# Sheet1.net
KiCad netlist of a schematic drawn in Altium Designer
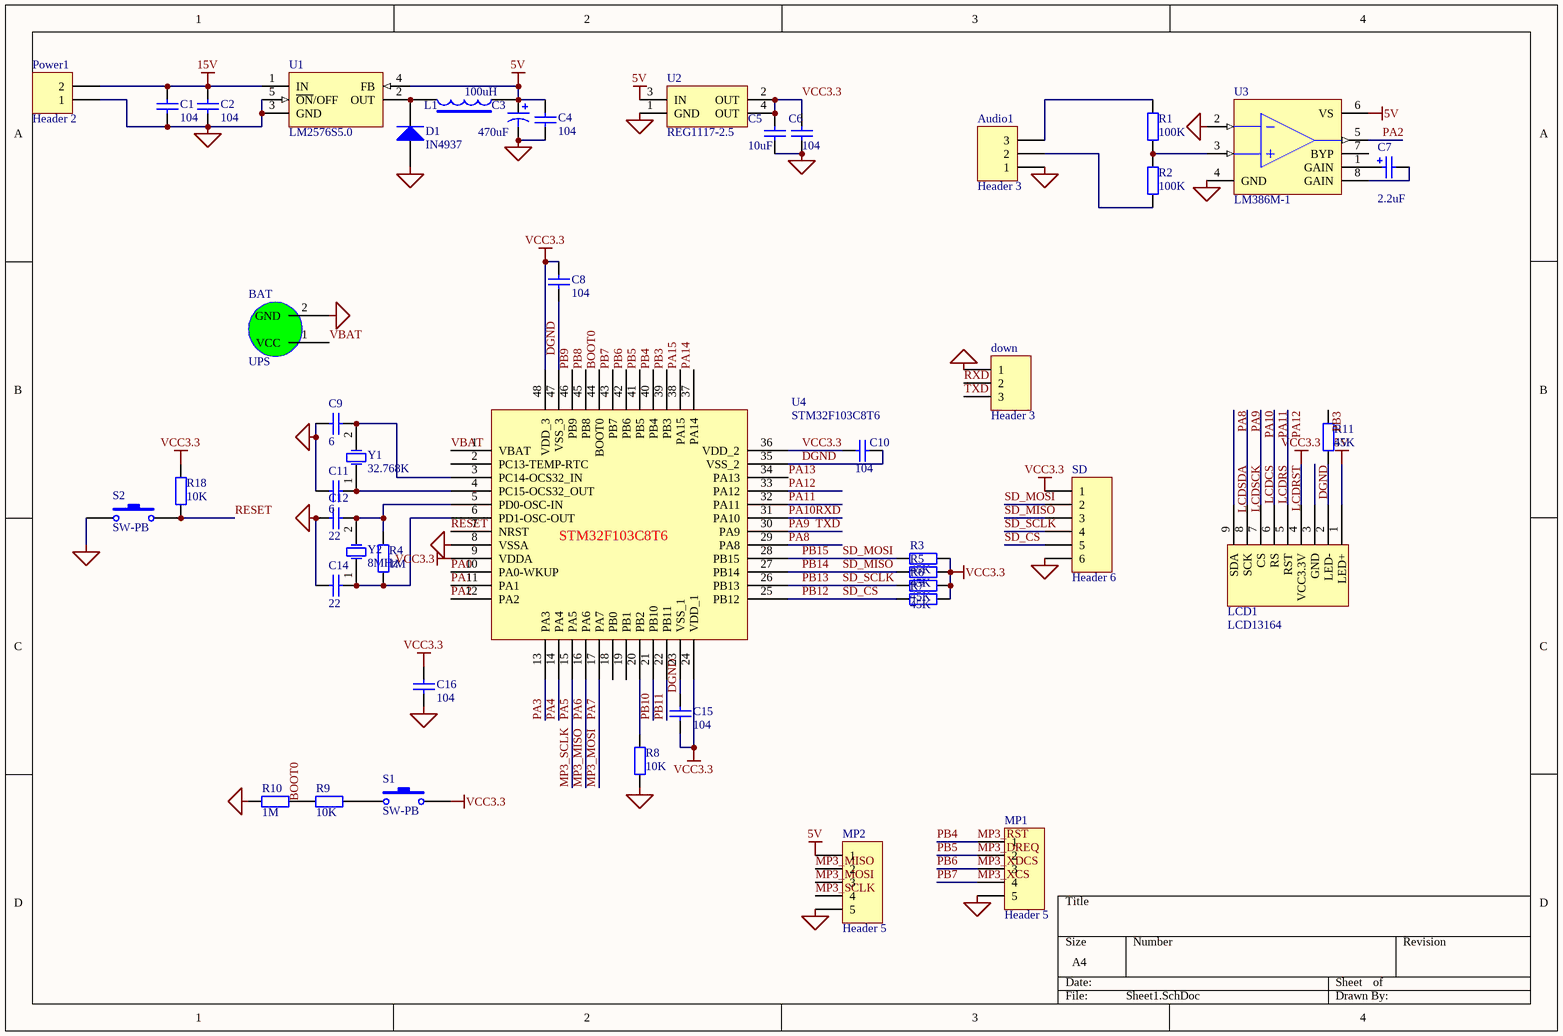
[diagram p0: Sheet1.SchDoc]

(export (version "E")
  (design (tool "Eeschema 10.0.6"))
  (components
    (comp (ref "Audio1")
      (value "Header 3")
      (footprint "HDR1X3")
      (description "Header, 3-Pin")
      (fields (field (name "PUBLISHER") "Altium Limited"))
      (libsource (lib "") (part "Header 3_1"))
    )
    (comp (ref "BAT") (value "UPS") (footprint "BAT") (libsource (lib "selfmade") (part "UPS")))
    (comp (ref "C1")
      (value "104")
      (footprint "1608[0603]")
      (description "Capacitor")
      (fields (field (name "PUBLISHER") "Altium Limited"))
      (libsource (lib "Miscellaneous Devices") (part "Cap"))
    )
    (comp (ref "C2")
      (value "104")
      (footprint "1608[0603]")
      (description "Capacitor")
      (fields (field (name "PUBLISHER") "Altium Limited"))
      (libsource (lib "Miscellaneous Devices") (part "Cap"))
    )
    (comp (ref "C3")
      (value "470uF")
      (footprint "RB.1/.2")
      (description "Polarized Capacitor (Radial)")
      (fields (field (name "PUBLISHER") "Altium Limited"))
      (libsource (lib "") (part "Cap Pol1_1"))
    )
    (comp (ref "C4")
      (value "104")
      (footprint "1608[0603]")
      (description "Capacitor")
      (fields (field (name "PUBLISHER") "Altium Limited"))
      (libsource (lib "Miscellaneous Devices") (part "Cap"))
    )
    (comp (ref "C5")
      (value "10uF")
      (footprint "2012[0805]")
      (description "Capacitor")
      (fields (field (name "PUBLISHER") "Altium Limited"))
      (libsource (lib "Miscellaneous Devices") (part "Cap"))
    )
    (comp (ref "C6")
      (value "104")
      (footprint "1608[0603]")
      (description "Capacitor")
      (fields (field (name "PUBLISHER") "Altium Limited"))
      (libsource (lib "Miscellaneous Devices") (part "Cap"))
    )
    (comp (ref "C7")
      (value "2.2uF")
      (footprint "2012[0805]")
      (description "Polarized Capacitor (Radial)")
      (fields (field (name "PUBLISHER") "Altium Limited"))
      (libsource (lib "Miscellaneous Devices") (part "Cap Pol1"))
    )
    (comp (ref "C8")
      (value "104")
      (footprint "1608[0603]")
      (description "Capacitor")
      (fields (field (name "PUBLISHER") "Altium Limited"))
      (libsource (lib "Miscellaneous Devices") (part "Cap"))
    )
    (comp (ref "C9")
      (value "6")
      (footprint "1608[0603]")
      (description "Capacitor")
      (fields (field (name "PUBLISHER") "Altium Limited"))
      (libsource (lib "Miscellaneous Devices") (part "Cap"))
    )
    (comp (ref "C10")
      (value "104")
      (footprint "1608[0603]")
      (description "Capacitor")
      (fields (field (name "PUBLISHER") "Altium Limited"))
      (libsource (lib "Miscellaneous Devices") (part "Cap"))
    )
    (comp (ref "C11")
      (value "6")
      (footprint "1608[0603]")
      (description "Capacitor")
      (fields (field (name "PUBLISHER") "Altium Limited"))
      (libsource (lib "Miscellaneous Devices") (part "Cap"))
    )
    (comp (ref "C12")
      (value "22")
      (footprint "1608[0603]")
      (description "Capacitor")
      (fields (field (name "PUBLISHER") "Altium Limited"))
      (libsource (lib "Miscellaneous Devices") (part "Cap"))
    )
    (comp (ref "C14")
      (value "22")
      (footprint "1608[0603]")
      (description "Capacitor")
      (fields (field (name "PUBLISHER") "Altium Limited"))
      (libsource (lib "Miscellaneous Devices") (part "Cap"))
    )
    (comp (ref "C15")
      (value "104")
      (footprint "1608[0603]")
      (description "Capacitor")
      (fields (field (name "PUBLISHER") "Altium Limited"))
      (libsource (lib "Miscellaneous Devices") (part "Cap"))
    )
    (comp (ref "C16")
      (value "104")
      (footprint "1608[0603]")
      (description "Capacitor")
      (fields (field (name "PUBLISHER") "Altium Limited"))
      (libsource (lib "Miscellaneous Devices") (part "Cap"))
    )
    (comp (ref "D1")
      (value "IN4937")
      (footprint "DIODE-0.4")
      (description "1 Amp General Purpose Rectifier")
      (fields (field (name "PUBLISHER") "Altium Limited"))
      (libsource (lib "Miscellaneous Devices") (part "Diode 1N4007"))
    )
    (comp (ref "down")
      (value "Header 3")
      (footprint "HDR1X3")
      (description "Header, 3-Pin")
      (fields (field (name "PUBLISHER") "Altium Limited"))
      (libsource (lib "Miscellaneous Connectors") (part "Header 3"))
    )
    (comp (ref "L1") (value "100uH") (footprint "HDR1X2") (libsource (lib "*") (part "INDUCTOR2")))
    (comp (ref "LCD1") (value "LCD13164") (footprint "HDR1X9") (libsource (lib "selfmade") (part "LCD13164")))
    (comp (ref "MP1")
      (value "Header 5")
      (footprint "HDR1X5")
      (description "Header, 5-Pin")
      (fields (field (name "PUBLISHER") "Altium Limited"))
      (libsource (lib "Miscellaneous Connectors") (part "Header 5"))
    )
    (comp (ref "MP2")
      (value "Header 5")
      (footprint "HDR1X5")
      (description "Header, 5-Pin")
      (fields (field (name "PUBLISHER") "Altium Limited"))
      (libsource (lib "Miscellaneous Connectors") (part "Header 5"))
    )
    (comp (ref "Power1")
      (value "Header 2")
      (footprint "HDR1X2")
      (description "Header, 2-Pin")
      (fields (field (name "PUBLISHER") "Altium Limited"))
      (libsource (lib "Miscellaneous Connectors") (part "Header 2"))
    )
    (comp (ref "R1")
      (value "100K")
      (footprint "1608[0603]")
      (description "Resistor")
      (fields (field (name "PUBLISHER") "Altium Limited"))
      (libsource (lib "") (part "Res2_2"))
    )
    (comp (ref "R2")
      (value "100K")
      (footprint "1608[0603]")
      (description "Resistor")
      (fields (field (name "PUBLISHER") "Altium Limited"))
      (libsource (lib "") (part "Res2_2"))
    )
    (comp (ref "R3")
      (value "45K")
      (footprint "1608[0603]")
      (description "Resistor")
      (fields (field (name "PUBLISHER") "Altium Limited"))
      (libsource (lib "") (part "Res2_1"))
    )
    (comp (ref "R4")
      (value "1M")
      (footprint "1608[0603]")
      (description "Resistor")
      (fields (field (name "PUBLISHER") "Altium Limited"))
      (libsource (lib "") (part "Res2_2"))
    )
    (comp (ref "R5")
      (value "45K")
      (footprint "1608[0603]")
      (description "Resistor")
      (fields (field (name "PUBLISHER") "Altium Limited"))
      (libsource (lib "") (part "Res2_1"))
    )
    (comp (ref "R6")
      (value "45K")
      (footprint "1608[0603]")
      (description "Resistor")
      (fields (field (name "PUBLISHER") "Altium Limited"))
      (libsource (lib "") (part "Res2_1"))
    )
    (comp (ref "R7")
      (value "45K")
      (footprint "1608[0603]")
      (description "Resistor")
      (fields (field (name "PUBLISHER") "Altium Limited"))
      (libsource (lib "") (part "Res2_1"))
    )
    (comp (ref "R8")
      (value "10K")
      (footprint "1608[0603]")
      (description "Resistor")
      (fields (field (name "PUBLISHER") "Altium Limited"))
      (libsource (lib "") (part "Res2_2"))
    )
    (comp (ref "R9")
      (value "10K")
      (footprint "1608[0603]")
      (description "Resistor")
      (fields (field (name "PUBLISHER") "Altium Limited"))
      (libsource (lib "Miscellaneous Devices") (part "Res2"))
    )
    (comp (ref "R10")
      (value "1M")
      (footprint "1608[0603]")
      (description "Resistor")
      (fields (field (name "PUBLISHER") "Altium Limited"))
      (libsource (lib "Miscellaneous Devices") (part "Res2"))
    )
    (comp (ref "R11")
      (value "45K")
      (footprint "1608[0603]")
      (description "Resistor")
      (fields (field (name "PUBLISHER") "Altium Limited"))
      (libsource (lib "") (part "Res2_2"))
    )
    (comp (ref "R18")
      (value "10K")
      (footprint "1608[0603]")
      (description "Resistor")
      (fields (field (name "PUBLISHER") "Altium Limited"))
      (libsource (lib "") (part "Res2_2"))
    )
    (comp (ref "S1")
      (value "SW-PB")
      (footprint "SPST-2")
      (description "Switch")
      (fields (field (name "PUBLISHER") "Altium Limited"))
      (libsource (lib "Miscellaneous Devices") (part "SW-PB"))
    )
    (comp (ref "S2")
      (value "SW-PB")
      (footprint "SPST-2")
      (description "Switch")
      (fields (field (name "PUBLISHER") "Altium Limited"))
      (libsource (lib "Miscellaneous Devices") (part "SW-PB"))
    )
    (comp (ref "SD")
      (value "Header 6")
      (footprint "HDR1X6")
      (description "Header, 6-Pin")
      (fields (field (name "PUBLISHER") "Altium Limited"))
      (libsource (lib "Miscellaneous Connectors") (part "Header 6"))
    )
    (comp (ref "U1")
      (value "LM2576S5.0")
      (footprint "HDR1X5")
      (description "Simple Switcher 3A Step Down Voltage Regulator")
      (fields (field (name "PUBLISHER") "Altium Limited"))
      (libsource (lib "NSC Power Mgt Switching Regulator") (part "LM2576S5.0"))
    )
    (comp (ref "U2")
      (value "REG1117-2.5")
      (footprint "ZZ311")
      (description "800mA and 1A Low Dropout Positive Regulator 2.85V, 3.3V, 5V, and Adjustable")
      (fields (field (name "PUBLISHER") "Altium Limited"))
      (libsource (lib "BB Power Mgt Voltage Regulator") (part "REG1117-3.3"))
    )
    (comp (ref "U3")
      (value "LM386M-1")
      (footprint "SOP-8 - duplicate")
      (description "Low-Voltage Audio Power Amplifier")
      (fields (field (name "PUBLISHER") "Altium Limited"))
      (libsource (lib "NSC Audio Power Amplifier") (part "LM386M-1"))
    )
    (comp (ref "U4") (value "STM32F103C8T6") (libsource (lib "STM32103C8T6") (part "STM32F103C8T6")))
    (comp (ref "Y1")
      (value "32.768K")
      (footprint "BCY-W2/D3.1")
      (description "Crystal Oscillator")
      (fields (field (name "PUBLISHER") "Altium Limited"))
      (libsource (lib "Miscellaneous Devices") (part "XTAL"))
    )
    (comp (ref "Y2")
      (value "8MHz")
      (footprint "SPST-2")
      (description "Crystal Oscillator")
      (fields (field (name "PUBLISHER") "Altium Limited"))
      (libsource (lib "Miscellaneous Devices") (part "XTAL"))
    )
  )
  (nets
    (net (code "1") (name "/BOOT0") (class "Default")
      (node (ref "R10") (pin "2") (pinfunction "2_2") (pintype "passive"))
      (node (ref "R9") (pin "1") (pinfunction "1_1") (pintype "passive"))
      (node (ref "U4") (pin "44") (pinfunction "BOOT0_44") (pintype "passive"))
    )
    (net (code "2") (name "/LCDCS") (class "Default")
      (node (ref "LCD1") (pin "7") (pinfunction "CS_7") (pintype "passive"))
      (node (ref "U4") (pin "31") (pinfunction "PA10_31") (pintype "passive"))
      (node (ref "down") (pin "2") (pinfunction "2_2") (pintype "passive"))
    )
    (net (code "3") (name "/LCDRS") (class "Default")
      (node (ref "LCD1") (pin "6") (pinfunction "RS_6") (pintype "passive"))
      (node (ref "U4") (pin "32") (pinfunction "PA11_32") (pintype "passive"))
    )
    (net (code "4") (name "/LCDRST") (class "Default")
      (node (ref "LCD1") (pin "5") (pinfunction "RST_5") (pintype "passive"))
      (node (ref "U4") (pin "33") (pinfunction "PA12_33") (pintype "passive"))
    )
    (net (code "5") (name "/LCDSCK") (class "Default")
      (node (ref "LCD1") (pin "8") (pinfunction "SCK_8") (pintype "passive"))
      (node (ref "U4") (pin "30") (pinfunction "PA9_30") (pintype "passive"))
      (node (ref "down") (pin "3") (pinfunction "3_3") (pintype "passive"))
    )
    (net (code "6") (name "/LCDSDA") (class "Default")
      (node (ref "LCD1") (pin "9") (pinfunction "SDA_9") (pintype "passive"))
      (node (ref "U4") (pin "29") (pinfunction "PA8_29") (pintype "passive"))
    )
    (net (code "7") (name "/MP3_DREQ") (class "Default")
      (node (ref "MP1") (pin "2") (pinfunction "2_2") (pintype "passive"))
      (node (ref "U4") (pin "41") (pinfunction "PB5_41") (pintype "passive"))
    )
    (net (code "8") (name "/MP3_MISO") (class "Default")
      (node (ref "MP2") (pin "2") (pinfunction "2_2") (pintype "passive"))
      (node (ref "U4") (pin "16") (pinfunction "PA6_16") (pintype "passive"))
    )
    (net (code "9") (name "/MP3_MOSI") (class "Default")
      (node (ref "MP2") (pin "3") (pinfunction "3_3") (pintype "passive"))
      (node (ref "U4") (pin "17") (pinfunction "PA7_17") (pintype "passive"))
    )
    (net (code "10") (name "/MP3_RST") (class "Default")
      (node (ref "MP1") (pin "1") (pinfunction "1_1") (pintype "passive"))
      (node (ref "U4") (pin "40") (pinfunction "PB4_40") (pintype "passive"))
    )
    (net (code "11") (name "/MP3_SCLK") (class "Default")
      (node (ref "MP2") (pin "4") (pinfunction "4_4") (pintype "passive"))
      (node (ref "U4") (pin "15") (pinfunction "PA5_15") (pintype "passive"))
    )
    (net (code "12") (name "/MP3_XCS") (class "Default")
      (node (ref "MP1") (pin "4") (pinfunction "4_4") (pintype "passive"))
      (node (ref "U4") (pin "43") (pinfunction "PB7_43") (pintype "passive"))
    )
    (net (code "13") (name "/MP3_XDCS") (class "Default")
      (node (ref "MP1") (pin "3") (pinfunction "3_3") (pintype "passive"))
      (node (ref "U4") (pin "42") (pinfunction "PB6_42") (pintype "passive"))
    )
    (net (code "14") (name "/PA0") (class "Default")
      (node (ref "U4") (pin "10") (pinfunction "PA0-WKUP_10") (pintype "passive"))
    )
    (net (code "15") (name "/PA1") (class "Default")
      (node (ref "U4") (pin "11") (pinfunction "PA1_11") (pintype "passive"))
    )
    (net (code "16") (name "/PA2") (class "Default")
      (node (ref "U3") (pin "5") (pinfunction "OUT_5") (pintype "output"))
      (node (ref "U4") (pin "12") (pinfunction "PA2_12") (pintype "passive"))
    )
    (net (code "17") (name "/PA3") (class "Default")
      (node (ref "U4") (pin "13") (pinfunction "PA3_13") (pintype "passive"))
    )
    (net (code "18") (name "/PA4") (class "Default")
      (node (ref "U4") (pin "14") (pinfunction "PA4_14") (pintype "passive"))
    )
    (net (code "19") (name "/PA13") (class "Default")
      (node (ref "U4") (pin "34") (pinfunction "PA13_34") (pintype "passive"))
    )
    (net (code "20") (name "/PA14") (class "Default")
      (node (ref "U4") (pin "37") (pinfunction "PA14_37") (pintype "passive"))
    )
    (net (code "21") (name "/PA15") (class "Default")
      (node (ref "U4") (pin "38") (pinfunction "PA15_38") (pintype "passive"))
    )
    (net (code "22") (name "/PB3") (class "Default")
      (node (ref "R11") (pin "1") (pinfunction "1_1") (pintype "passive"))
      (node (ref "U4") (pin "39") (pinfunction "PB3_39") (pintype "passive"))
    )
    (net (code "23") (name "/PB8") (class "Default")
      (node (ref "U4") (pin "45") (pinfunction "PB8_45") (pintype "passive"))
    )
    (net (code "24") (name "/PB9") (class "Default")
      (node (ref "U4") (pin "46") (pinfunction "PB9_46") (pintype "passive"))
    )
    (net (code "25") (name "/PB10") (class "Default")
      (node (ref "U4") (pin "21") (pinfunction "PB10_21") (pintype "passive"))
    )
    (net (code "26") (name "/PB11") (class "Default")
      (node (ref "U4") (pin "22") (pinfunction "PB11_22") (pintype "passive"))
    )
    (net (code "27") (name "/PB12") (class "Default")
      (node (ref "R7") (pin "2") (pinfunction "2_2") (pintype "passive"))
      (node (ref "SD") (pin "5") (pinfunction "5_5") (pintype "passive"))
      (node (ref "U4") (pin "25") (pinfunction "PB12_25") (pintype "passive"))
    )
    (net (code "28") (name "/PB13") (class "Default")
      (node (ref "R6") (pin "2") (pinfunction "2_2") (pintype "passive"))
      (node (ref "SD") (pin "4") (pinfunction "4_4") (pintype "passive"))
      (node (ref "U4") (pin "26") (pinfunction "PB13_26") (pintype "passive"))
    )
    (net (code "29") (name "/PB14") (class "Default")
      (node (ref "R5") (pin "2") (pinfunction "2_2") (pintype "passive"))
      (node (ref "SD") (pin "3") (pinfunction "3_3") (pintype "passive"))
      (node (ref "U4") (pin "27") (pinfunction "PB14_27") (pintype "passive"))
    )
    (net (code "30") (name "/PB15") (class "Default")
      (node (ref "R3") (pin "2") (pinfunction "2_2") (pintype "passive"))
      (node (ref "SD") (pin "2") (pinfunction "2_2") (pintype "passive"))
      (node (ref "U4") (pin "28") (pinfunction "PB15_28") (pintype "passive"))
    )
    (net (code "31") (name "/RESET") (class "Default")
      (node (ref "R18") (pin "2") (pinfunction "2_2") (pintype "passive"))
      (node (ref "S2") (pin "2") (pinfunction "2_2") (pintype "passive"))
      (node (ref "U4") (pin "7") (pinfunction "NRST_7") (pintype "passive"))
    )
    (net (code "32") (name "/VBAT") (class "Default")
      (node (ref "BAT") (pin "1") (pinfunction "VCC_1") (pintype "passive"))
      (node (ref "U4") (pin "1") (pinfunction "VBAT_1") (pintype "passive"))
    )
    (net (code "33") (name "5V") (class "Default")
      (node (ref "C3") (pin "1") (pinfunction "1_1") (pintype "passive"))
      (node (ref "C4") (pin "1") (pinfunction "1_1") (pintype "passive"))
      (node (ref "L1") (pin "1") (pinfunction "1_1") (pintype "passive"))
      (node (ref "LCD1") (pin "1") (pinfunction "LED+_1") (pintype "passive"))
      (node (ref "MP2") (pin "1") (pinfunction "1_1") (pintype "passive"))
      (node (ref "U1") (pin "4") (pinfunction "FB_4") (pintype "input"))
      (node (ref "U2") (pin "3") (pinfunction "IN_3") (pintype "power_in"))
      (node (ref "U3") (pin "6") (pinfunction "VS_6") (pintype "power_in"))
    )
    (net (code "34") (name "15V") (class "Default")
      (node (ref "C1") (pin "1") (pinfunction "1_1") (pintype "passive"))
      (node (ref "C2") (pin "1") (pinfunction "1_1") (pintype "passive"))
      (node (ref "Power1") (pin "2") (pinfunction "2_2") (pintype "passive"))
      (node (ref "U1") (pin "1") (pinfunction "IN_1") (pintype "power_in"))
    )
    (net (code "35") (name "DGND") (class "Default")
      (node (ref "Audio1") (pin "1") (pinfunction "1_1") (pintype "passive"))
      (node (ref "BAT") (pin "2") (pinfunction "GND_2") (pintype "passive"))
      (node (ref "C1") (pin "2") (pinfunction "2_2") (pintype "passive"))
      (node (ref "C10") (pin "2") (pinfunction "2_2") (pintype "passive"))
      (node (ref "C11") (pin "1") (pinfunction "1_1") (pintype "passive"))
      (node (ref "C12") (pin "1") (pinfunction "1_1") (pintype "passive"))
      (node (ref "C14") (pin "1") (pinfunction "1_1") (pintype "passive"))
      (node (ref "C15") (pin "1") (pinfunction "1_1") (pintype "passive"))
      (node (ref "C16") (pin "1") (pinfunction "1_1") (pintype "passive"))
      (node (ref "C2") (pin "2") (pinfunction "2_2") (pintype "passive"))
      (node (ref "C3") (pin "2") (pinfunction "2_2") (pintype "passive"))
      (node (ref "C4") (pin "2") (pinfunction "2_2") (pintype "passive"))
      (node (ref "C5") (pin "2") (pinfunction "2_2") (pintype "passive"))
      (node (ref "C6") (pin "1") (pinfunction "1_1") (pintype "passive"))
      (node (ref "C8") (pin "1") (pinfunction "1_1") (pintype "passive"))
      (node (ref "C9") (pin "1") (pinfunction "1_1") (pintype "passive"))
      (node (ref "D1") (pin "1") (pinfunction "A_1") (pintype "passive"))
      (node (ref "LCD1") (pin "3") (pinfunction "GND_3") (pintype "passive"))
      (node (ref "MP1") (pin "5") (pinfunction "5_5") (pintype "passive"))
      (node (ref "MP2") (pin "5") (pinfunction "5_5") (pintype "passive"))
      (node (ref "Power1") (pin "1") (pinfunction "1_1") (pintype "passive"))
      (node (ref "R10") (pin "1") (pinfunction "1_1") (pintype "passive"))
      (node (ref "R8") (pin "2") (pinfunction "2_2") (pintype "passive"))
      (node (ref "S2") (pin "1") (pinfunction "1_1") (pintype "passive"))
      (node (ref "SD") (pin "6") (pinfunction "6_6") (pintype "passive"))
      (node (ref "U1") (pin "3") (pinfunction "GND_3") (pintype "power_in"))
      (node (ref "U1") (pin "5") (pinfunction "~{ON}/OFF_5") (pintype "input"))
      (node (ref "U2") (pin "1") (pinfunction "GND_1") (pintype "power_in"))
      (node (ref "U3") (pin "2") (pinfunction "IN-_2") (pintype "input"))
      (node (ref "U3") (pin "4") (pinfunction "GND_4") (pintype "power_in"))
      (node (ref "U4") (pin "23") (pinfunction "VSS_1_23") (pintype "passive"))
      (node (ref "U4") (pin "35") (pinfunction "VSS_2_35") (pintype "passive"))
      (node (ref "U4") (pin "47") (pinfunction "VSS_3_47") (pintype "passive"))
      (node (ref "U4") (pin "8") (pinfunction "VSSA_8") (pintype "passive"))
      (node (ref "down") (pin "1") (pinfunction "1_1") (pintype "passive"))
    )
    (net (code "36") (name "Net-(Audio1-Pad2)") (class "Default")
      (node (ref "Audio1") (pin "2") (pinfunction "2_2") (pintype "passive"))
      (node (ref "R2") (pin "2") (pinfunction "2_2") (pintype "passive"))
    )
    (net (code "37") (name "Net-(Audio1-Pad3)") (class "Default")
      (node (ref "Audio1") (pin "3") (pinfunction "3_3") (pintype "passive"))
      (node (ref "R1") (pin "1") (pinfunction "1_1") (pintype "passive"))
    )
    (net (code "38") (name "Net-(C7-Pad1)") (class "Default")
      (node (ref "C7") (pin "1") (pinfunction "1_1") (pintype "passive"))
      (node (ref "U3") (pin "1") (pinfunction "GAIN_1") (pintype "passive"))
    )
    (net (code "39") (name "Net-(C7-Pad2)") (class "Default")
      (node (ref "C7") (pin "2") (pinfunction "2_2") (pintype "passive"))
      (node (ref "U3") (pin "8") (pinfunction "GAIN_8") (pintype "passive"))
    )
    (net (code "40") (name "Net-(D1-K)") (class "Default")
      (node (ref "D1") (pin "2") (pinfunction "K_2") (pintype "passive"))
      (node (ref "L1") (pin "2") (pinfunction "2_2") (pintype "passive"))
      (node (ref "U1") (pin "2") (pinfunction "OUT_2") (pintype "power_in"))
    )
    (net (code "41") (name "Net-(LCD1-LED-)") (class "Default")
      (node (ref "LCD1") (pin "2") (pinfunction "LED-_2") (pintype "passive"))
      (node (ref "R11") (pin "2") (pinfunction "2_2") (pintype "passive"))
    )
    (net (code "42") (name "Net-(R9-Pad2)") (class "Default")
      (node (ref "R9") (pin "2") (pinfunction "2_2") (pintype "passive"))
      (node (ref "S1") (pin "1") (pinfunction "1_1") (pintype "passive"))
    )
    (net (code "43") (name "Net-(U3-IN+)") (class "Default")
      (node (ref "R1") (pin "2") (pinfunction "2_2") (pintype "passive"))
      (node (ref "R2") (pin "1") (pinfunction "1_1") (pintype "passive"))
      (node (ref "U3") (pin "3") (pinfunction "IN+_3") (pintype "input"))
    )
    (net (code "44") (name "Net-(U4-PB2)") (class "Default")
      (node (ref "R8") (pin "1") (pinfunction "1_1") (pintype "passive"))
      (node (ref "U4") (pin "20") (pinfunction "PB2_20") (pintype "passive"))
    )
    (net (code "45") (name "Net-(U4-PC14-OCS32_IN)") (class "Default")
      (node (ref "C9") (pin "2") (pinfunction "2_2") (pintype "passive"))
      (node (ref "U4") (pin "3") (pinfunction "PC14-OCS32_IN_3") (pintype "passive"))
      (node (ref "Y1") (pin "2") (pinfunction "OSC2_2") (pintype "passive"))
    )
    (net (code "46") (name "Net-(U4-PC15-OCS32_OUT)") (class "Default")
      (node (ref "C11") (pin "2") (pinfunction "2_2") (pintype "passive"))
      (node (ref "U4") (pin "4") (pinfunction "PC15-OCS32_OUT_4") (pintype "passive"))
      (node (ref "Y1") (pin "1") (pinfunction "OSC1_1") (pintype "passive"))
    )
    (net (code "47") (name "Net-(U4-PD0-OSC-IN)") (class "Default")
      (node (ref "C12") (pin "2") (pinfunction "2_2") (pintype "passive"))
      (node (ref "R4") (pin "1") (pinfunction "1_1") (pintype "passive"))
      (node (ref "U4") (pin "5") (pinfunction "PD0-OSC-IN_5") (pintype "passive"))
      (node (ref "Y2") (pin "2") (pinfunction "OSC2_2") (pintype "passive"))
    )
    (net (code "48") (name "Net-(U4-PD1-OSC-OUT)") (class "Default")
      (node (ref "C14") (pin "2") (pinfunction "2_2") (pintype "passive"))
      (node (ref "R4") (pin "2") (pinfunction "2_2") (pintype "passive"))
      (node (ref "U4") (pin "6") (pinfunction "PD1-OSC-OUT_6") (pintype "passive"))
      (node (ref "Y2") (pin "1") (pinfunction "OSC1_1") (pintype "passive"))
    )
    (net (code "49") (name "VCC3.3") (class "Default")
      (node (ref "C10") (pin "1") (pinfunction "1_1") (pintype "passive"))
      (node (ref "C15") (pin "2") (pinfunction "2_2") (pintype "passive"))
      (node (ref "C16") (pin "2") (pinfunction "2_2") (pintype "passive"))
      (node (ref "C5") (pin "1") (pinfunction "1_1") (pintype "passive"))
      (node (ref "C6") (pin "2") (pinfunction "2_2") (pintype "passive"))
      (node (ref "C8") (pin "2") (pinfunction "2_2") (pintype "passive"))
      (node (ref "LCD1") (pin "4") (pinfunction "VCC3.3V_4") (pintype "passive"))
      (node (ref "R18") (pin "1") (pinfunction "1_1") (pintype "passive"))
      (node (ref "R3") (pin "1") (pinfunction "1_1") (pintype "passive"))
      (node (ref "R5") (pin "1") (pinfunction "1_1") (pintype "passive"))
      (node (ref "R6") (pin "1") (pinfunction "1_1") (pintype "passive"))
      (node (ref "R7") (pin "1") (pinfunction "1_1") (pintype "passive"))
      (node (ref "S1") (pin "2") (pinfunction "2_2") (pintype "passive"))
      (node (ref "SD") (pin "1") (pinfunction "1_1") (pintype "passive"))
      (node (ref "U2") (pin "2") (pinfunction "OUT_2") (pintype "power_in"))
      (node (ref "U2") (pin "4") (pinfunction "OUT_4") (pintype "power_in"))
      (node (ref "U4") (pin "24") (pinfunction "VDD_1_24") (pintype "passive"))
      (node (ref "U4") (pin "36") (pinfunction "VDD_2_36") (pintype "passive"))
      (node (ref "U4") (pin "48") (pinfunction "VDD_3_48") (pintype "passive"))
      (node (ref "U4") (pin "9") (pinfunction "VDDA_9") (pintype "passive"))
    )
    (net (code "50") (name "unconnected-(U3-BYP-Pad7)") (class "Default")
      (node (ref "U3") (pin "7") (pinfunction "BYP_7") (pintype "passive"))
    )
    (net (code "51") (name "unconnected-(U4-PB0-Pad18)") (class "Default")
      (node (ref "U4") (pin "18") (pinfunction "PB0_18") (pintype "passive"))
    )
    (net (code "52") (name "unconnected-(U4-PB1-Pad19)") (class "Default")
      (node (ref "U4") (pin "19") (pinfunction "PB1_19") (pintype "passive"))
    )
    (net (code "53") (name "unconnected-(U4-PC13-TEMP-RTC-Pad2)") (class "Default")
      (node (ref "U4") (pin "2") (pinfunction "PC13-TEMP-RTC_2") (pintype "passive"))
    )
  )
)
